# SparkFun_XBee3_Cat1_Smart_Modem_Regulate.net
KiCad netlist of a schematic drawn in EAGLE
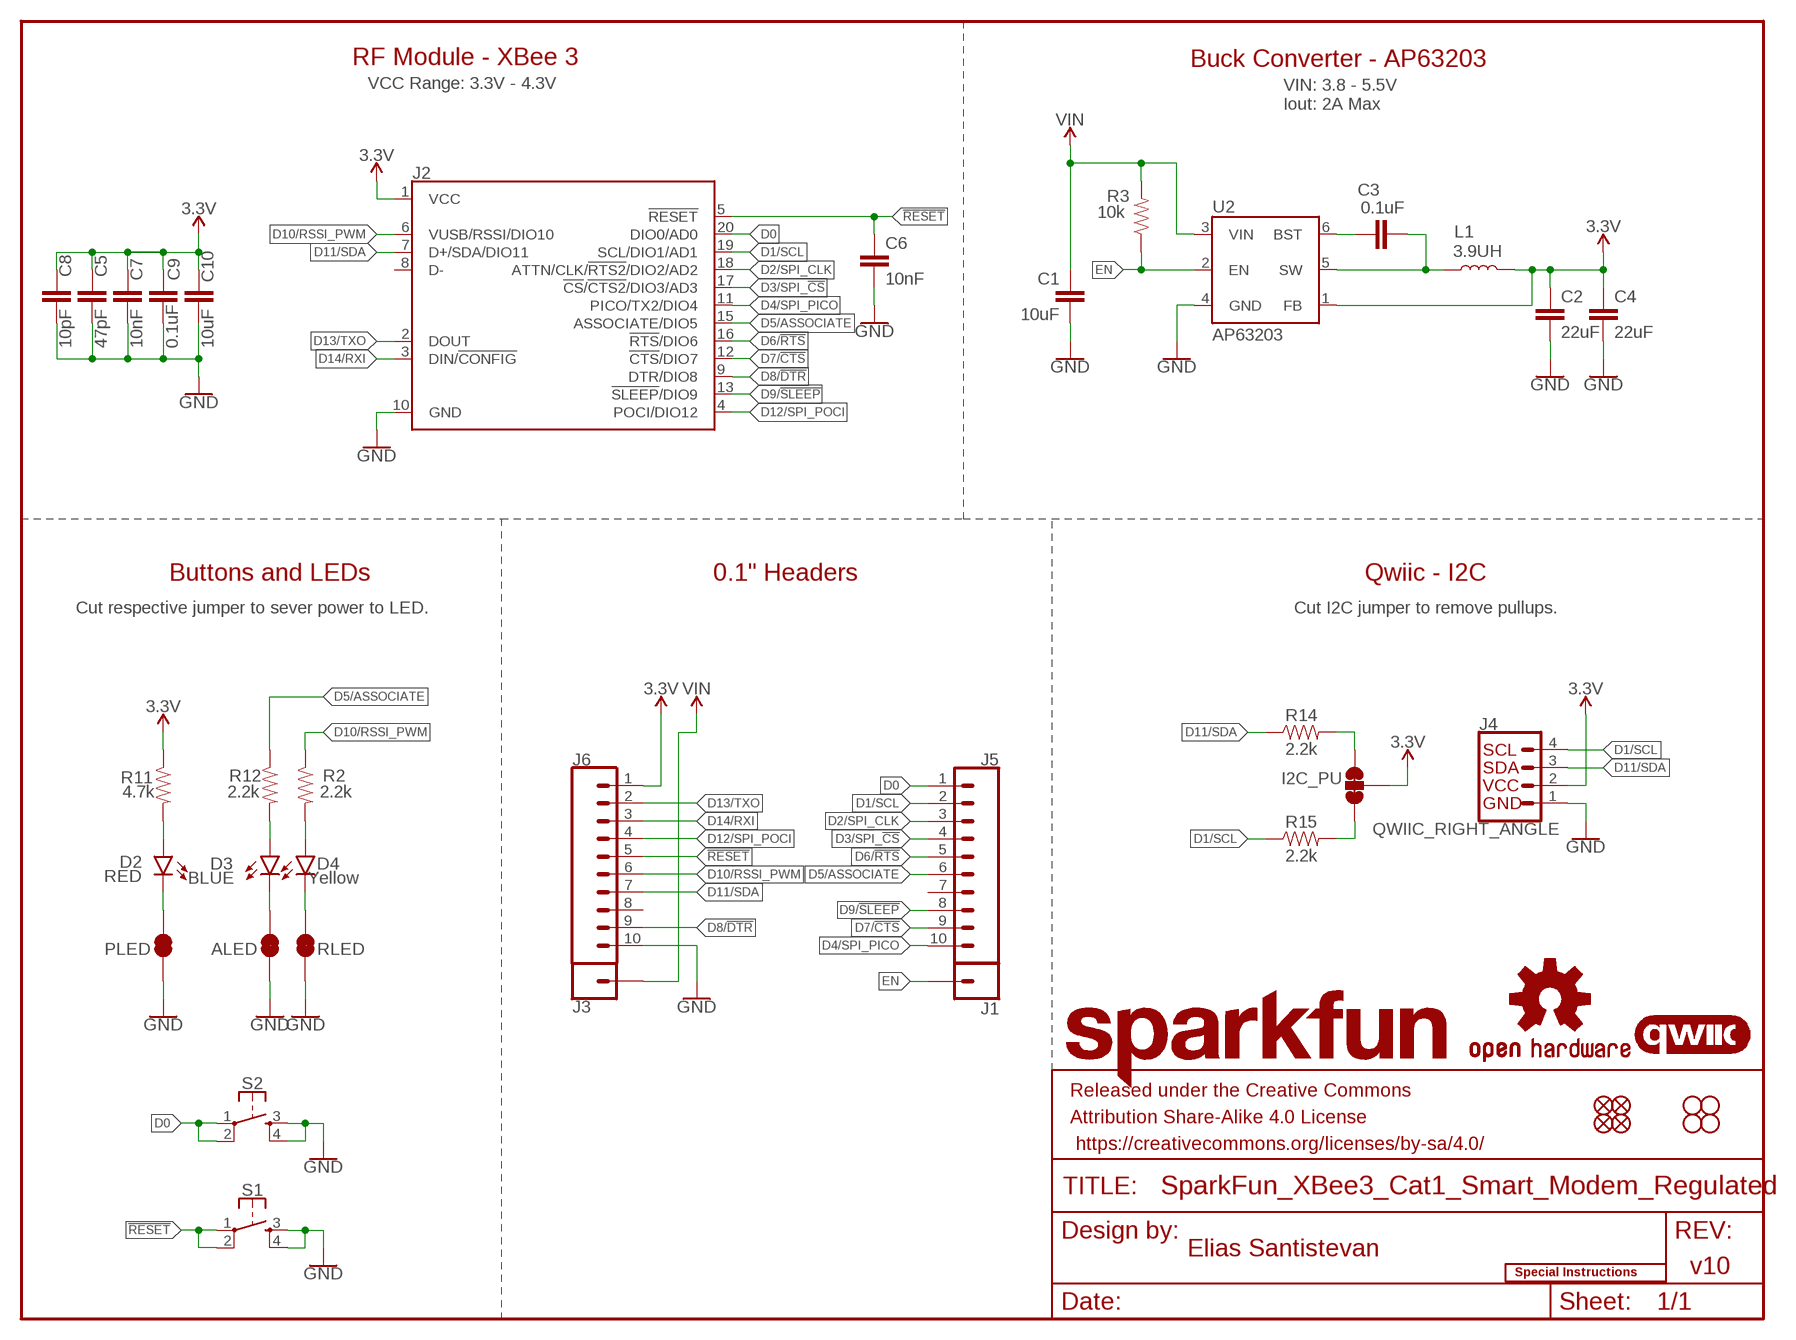
[diagram p0: schematic, sheet 1]

(export (version "E")
  (design (tool "Eeschema 10.0.6"))
  (components
    (comp (ref "ALED")
      (value "JUMPER-SMT_2_NC_TRACE_SILK")
      (footprint "eagle-import:SMT-JUMPER_2_NC_TRACE_SILK")
      (libsource (lib "eagle-import") (part "JUMPER-SMT_2_NC_TRACE_SILK"))
    )
    (comp (ref "C1")
      (value "10uF")
      (footprint "eagle-import:1210")
      (libsource (lib "eagle-import") (part "10UF-1210-50V-20%"))
    )
    (comp (ref "C2")
      (value "22uF")
      (footprint "eagle-import:0603")
      (libsource (lib "eagle-import") (part "22UF-0603-6.3V-20%"))
    )
    (comp (ref "C3")
      (value "0.1uF")
      (footprint "eagle-import:0603")
      (libsource (lib "eagle-import") (part "0.1UF-0603-25V-5%"))
    )
    (comp (ref "C4")
      (value "22uF")
      (footprint "eagle-import:0603")
      (libsource (lib "eagle-import") (part "22UF-0603-6.3V-20%"))
    )
    (comp (ref "C5")
      (value "47pF")
      (footprint "eagle-import:0603")
      (libsource (lib "eagle-import") (part "47PF-0603-50V-5%"))
    )
    (comp (ref "C6")
      (value "10nF")
      (footprint "eagle-import:0603")
      (libsource (lib "eagle-import") (part "10NF-0603-50V-10%"))
    )
    (comp (ref "C7")
      (value "10nF")
      (footprint "eagle-import:0603")
      (libsource (lib "eagle-import") (part "10NF-0603-50V-10%"))
    )
    (comp (ref "C8")
      (value "10pF")
      (footprint "eagle-import:0603")
      (libsource (lib "eagle-import") (part "10PF-0603-50V-5%"))
    )
    (comp (ref "C9")
      (value "0.1uF")
      (footprint "eagle-import:0603")
      (libsource (lib "eagle-import") (part "0.1UF-0603-25V-(+80/-20%)"))
    )
    (comp (ref "C10")
      (value "10uF")
      (footprint "eagle-import:0603")
      (libsource (lib "eagle-import") (part "10UF-0603-6.3V-20%"))
    )
    (comp (ref "D2")
      (value "RED")
      (footprint "eagle-import:LED-0603")
      (libsource (lib "eagle-import") (part "LED-RED_0603-KB"))
    )
    (comp (ref "D3")
      (value "BLUE")
      (footprint "eagle-import:LED-0603")
      (libsource (lib "eagle-import") (part "LED-BLUE0603"))
    )
    (comp (ref "D4")
      (value "Yellow")
      (footprint "eagle-import:LED-0603")
      (libsource (lib "eagle-import") (part "LED-YELLOW0603"))
    )
    (comp (ref "FD1")
      (value "FIDUCIAL1X2")
      (footprint "eagle-import:FIDUCIAL-1X2")
      (libsource (lib "eagle-import") (part "FIDUCIAL1X2"))
    )
    (comp (ref "FD2")
      (value "FIDUCIAL1X2")
      (footprint "eagle-import:FIDUCIAL-1X2")
      (libsource (lib "eagle-import") (part "FIDUCIAL1X2"))
    )
    (comp (ref "FD3")
      (value "FIDUCIAL1X2")
      (footprint "eagle-import:FIDUCIAL-1X2")
      (libsource (lib "eagle-import") (part "FIDUCIAL1X2"))
    )
    (comp (ref "FD4")
      (value "FIDUCIAL1X2")
      (footprint "eagle-import:FIDUCIAL-1X2")
      (libsource (lib "eagle-import") (part "FIDUCIAL1X2"))
    )
    (comp (ref "FRAME2")
      (value "FRAME-LETTER")
      (footprint "eagle-import:CREATIVE_COMMONS")
      (libsource (lib "eagle-import") (part "FRAME-LETTER"))
    )
    (comp (ref "H1")
      (value "STAND-OFFTIGHT")
      (footprint "eagle-import:STAND-OFF-TIGHT")
      (libsource (lib "eagle-import") (part "STAND-OFFTIGHT"))
    )
    (comp (ref "H2")
      (value "STAND-OFFTIGHT")
      (footprint "eagle-import:STAND-OFF-TIGHT")
      (libsource (lib "eagle-import") (part "STAND-OFFTIGHT"))
    )
    (comp (ref "H3")
      (value "STAND-OFFTIGHT")
      (footprint "eagle-import:STAND-OFF-TIGHT")
      (libsource (lib "eagle-import") (part "STAND-OFFTIGHT"))
    )
    (comp (ref "H4")
      (value "STAND-OFFTIGHT")
      (footprint "eagle-import:STAND-OFF-TIGHT")
      (libsource (lib "eagle-import") (part "STAND-OFFTIGHT"))
    )
    (comp (ref "I2C_PU")
      (value "JUMPER-SMT_3_2-NC_TRACE_SILK")
      (footprint "eagle-import:SMT-JUMPER_3_2-NC_TRACE_SILK")
      (libsource (lib "eagle-import") (part "JUMPER-SMT_3_2-NC_TRACE_SILK"))
    )
    (comp (ref "J1")
      (value "CONN_01PTH_NO_SILK_STAND")
      (footprint "eagle-import:1X01_NO_SILK_STAND")
      (libsource (lib "eagle-import") (part "CONN_01PTH_NO_SILK_STAND"))
    )
    (comp (ref "J2")
      (value "XBEE_UPDATEXBEE_SMD")
      (footprint "eagle-import:XBEE3-SMD")
      (libsource (lib "eagle-import") (part "XBEE_UPDATEXBEE_SMD"))
    )
    (comp (ref "J3")
      (value "CONN_01PTH_NO_SILK_STAND")
      (footprint "eagle-import:1X01_NO_SILK_STAND")
      (libsource (lib "eagle-import") (part "CONN_01PTH_NO_SILK_STAND"))
    )
    (comp (ref "J4")
      (value "QWIIC_RIGHT_ANGLE")
      (footprint "eagle-import:JST04_1MM_RA")
      (libsource (lib "eagle-import") (part "QWIIC_CONNECTORJS-1MM"))
    )
    (comp (ref "J5")
      (value "CONN_10NO_SILK_PTH_FEMALE")
      (footprint "eagle-import:1X10_NO_SILK")
      (libsource (lib "eagle-import") (part "CONN_10NO_SILK_PTH_FEMALE"))
    )
    (comp (ref "J6")
      (value "CONN_10NO_SILK_PTH_FEMALE")
      (footprint "eagle-import:1X10_NO_SILK")
      (libsource (lib "eagle-import") (part "CONN_10NO_SILK_PTH_FEMALE"))
    )
    (comp (ref "L1")
      (value "3.9UH")
      (footprint "eagle-import:INDUCTOR_3.9UH")
      (libsource (lib "eagle-import") (part "3.9UH"))
    )
    (comp (ref "LOGO1")
      (value "SPECIAL_INSTRUCTIONS-ORDERING")
      (footprint "eagle-import:ORDERING_INSTRUCTIONS")
      (libsource (lib "eagle-import") (part "SPECIAL_INSTRUCTIONS-ORDERING"))
    )
    (comp (ref "LOGO2")
      (value "OSHW-LOGOS")
      (footprint "eagle-import:OSHW-LOGO-S")
      (libsource (lib "eagle-import") (part "OSHW-LOGOS"))
    )
    (comp (ref "LOGO3")
      (value "QWIIC_LOGO_4MM")
      (footprint "eagle-import:QWIIC_4MM")
      (libsource (lib "eagle-import") (part "QWIIC_LOGO_4MM"))
    )
    (comp (ref "LOGO4")
      (value "SFE_LOGO_NAMEBLANK")
      (footprint "eagle-import:BLANK")
      (libsource (lib "eagle-import") (part "SFE_LOGO_NAMEBLANK"))
    )
    (comp (ref "PLED")
      (value "JUMPER-SMT_2_NC_TRACE_SILK")
      (footprint "eagle-import:SMT-JUMPER_2_NC_TRACE_SILK")
      (libsource (lib "eagle-import") (part "JUMPER-SMT_2_NC_TRACE_SILK"))
    )
    (comp (ref "R2")
      (value "2.2k")
      (footprint "eagle-import:0603")
      (libsource (lib "eagle-import") (part "2.2KOHM-0603-1/10W-1%"))
    )
    (comp (ref "R3")
      (value "10k")
      (footprint "eagle-import:0603")
      (libsource (lib "eagle-import") (part "10KOHM-0603-1/10W-1%"))
    )
    (comp (ref "R11")
      (value "4.7k")
      (footprint "eagle-import:0603")
      (libsource (lib "eagle-import") (part "4.7KOHM-0603-1/10W-1%"))
    )
    (comp (ref "R12")
      (value "2.2k")
      (footprint "eagle-import:0603")
      (libsource (lib "eagle-import") (part "2.2KOHM-0603-1/10W-1%"))
    )
    (comp (ref "R14")
      (value "2.2k")
      (footprint "eagle-import:0603")
      (libsource (lib "eagle-import") (part "2.2KOHM-0603-1/10W-1%"))
    )
    (comp (ref "R15")
      (value "2.2k")
      (footprint "eagle-import:0603")
      (libsource (lib "eagle-import") (part "2.2KOHM-0603-1/10W-1%"))
    )
    (comp (ref "RLED")
      (value "JUMPER-SMT_2_NC_TRACE_SILK")
      (footprint "eagle-import:SMT-JUMPER_2_NC_TRACE_SILK")
      (libsource (lib "eagle-import") (part "JUMPER-SMT_2_NC_TRACE_SILK"))
    )
    (comp (ref "S1")
      (value "MOMENTARY-SWITCH-SPST-2-SMD-5.2MM-TALL")
      (footprint "eagle-import:TACTILE_SWITCH_SMD_5.2MM")
      (libsource (lib "eagle-import") (part "MOMENTARY-SWITCH-SPST-2-SMD-5.2MM-TALL"))
    )
    (comp (ref "S2")
      (value "MOMENTARY-SWITCH-SPST-2-SMD-5.2MM-TALL")
      (footprint "eagle-import:TACTILE_SWITCH_SMD_5.2MM")
      (libsource (lib "eagle-import") (part "MOMENTARY-SWITCH-SPST-2-SMD-5.2MM-TALL"))
    )
    (comp (ref "U2")
      (value "AP63203")
      (footprint "eagle-import:SOT23-6")
      (libsource (lib "eagle-import") (part "AP63203"))
    )
  )
  (nets
    (net (code "1") (name "/D3{slash}SPI_~{CS}") (class "Default")
      (node (ref "J2") (pin "17") (pinfunction "~{CS}/~{CTS2}/DIO3/AD3_17") (pintype "bidirectional"))
      (node (ref "J5") (pin "4") (pinfunction "4_4") (pintype "passive"))
    )
    (net (code "2") (name "/D6{slash}~{RTS}") (class "Default")
      (node (ref "J2") (pin "16") (pinfunction "~{RTS}/DIO6_16") (pintype "input"))
      (node (ref "J5") (pin "5") (pinfunction "5_5") (pintype "passive"))
    )
    (net (code "3") (name "/D7{slash}~{CTS}") (class "Default")
      (node (ref "J2") (pin "12") (pinfunction "~{CTS}/DIO7_12") (pintype "output"))
      (node (ref "J5") (pin "9") (pinfunction "9_9") (pintype "passive"))
    )
    (net (code "4") (name "/D8{slash}~{DTR}") (class "Default")
      (node (ref "J2") (pin "9") (pinfunction "DTR/DIO8_9") (pintype "bidirectional"))
      (node (ref "J6") (pin "9") (pinfunction "9_9") (pintype "passive"))
    )
    (net (code "5") (name "/D9{slash}~{SLEEP}") (class "Default")
      (node (ref "J2") (pin "13") (pinfunction "~{SLEEP}/DIO9_13") (pintype "bidirectional"))
      (node (ref "J5") (pin "8") (pinfunction "8_8") (pintype "passive"))
    )
    (net (code "6") (name "/~{RESET}") (class "Default")
      (node (ref "C6") (pin "1") (pinfunction "1_1") (pintype "passive"))
      (node (ref "J2") (pin "5") (pinfunction "~{RESET}_5") (pintype "input"))
      (node (ref "J6") (pin "5") (pinfunction "5_5") (pintype "passive"))
      (node (ref "S1") (pin "1") (pinfunction "1_1") (pintype "passive"))
      (node (ref "S1") (pin "2") (pinfunction "2_2") (pintype "passive"))
    )
    (net (code "7") (name "3.3V") (class "Default")
      (node (ref "C10") (pin "1") (pinfunction "1_1") (pintype "passive"))
      (node (ref "C2") (pin "1") (pinfunction "1_1") (pintype "passive"))
      (node (ref "C4") (pin "1") (pinfunction "1_1") (pintype "passive"))
      (node (ref "C5") (pin "1") (pinfunction "1_1") (pintype "passive"))
      (node (ref "C7") (pin "1") (pinfunction "1_1") (pintype "passive"))
      (node (ref "C8") (pin "1") (pinfunction "1_1") (pintype "passive"))
      (node (ref "C9") (pin "1") (pinfunction "1_1") (pintype "passive"))
      (node (ref "I2C_PU") (pin "2") (pinfunction "2_2") (pintype "passive"))
      (node (ref "J2") (pin "1") (pinfunction "VCC_1") (pintype "power_in"))
      (node (ref "J4") (pin "2") (pinfunction "2_2") (pintype "power_in"))
      (node (ref "J6") (pin "1") (pinfunction "1_1") (pintype "passive"))
      (node (ref "L1") (pin "P$2") (pinfunction "2_P$2") (pintype "passive"))
      (node (ref "R11") (pin "1") (pinfunction "1_1") (pintype "passive"))
      (node (ref "U2") (pin "1") (pinfunction "FB_1") (pintype "bidirectional"))
    )
    (net (code "8") (name "D0") (class "Default")
      (node (ref "J2") (pin "20") (pinfunction "DIO0/AD0_20") (pintype "bidirectional"))
      (node (ref "J5") (pin "1") (pinfunction "1_1") (pintype "passive"))
      (node (ref "S2") (pin "1") (pinfunction "1_1") (pintype "passive"))
      (node (ref "S2") (pin "2") (pinfunction "2_2") (pintype "passive"))
    )
    (net (code "9") (name "D1{slash}SCL") (class "Default")
      (node (ref "J2") (pin "19") (pinfunction "SCL/DIO1/AD1_19") (pintype "bidirectional"))
      (node (ref "J4") (pin "4") (pinfunction "4_4") (pintype "passive"))
      (node (ref "J5") (pin "2") (pinfunction "2_2") (pintype "passive"))
      (node (ref "R15") (pin "1") (pinfunction "1_1") (pintype "passive"))
    )
    (net (code "10") (name "D2{slash}SPI_CLK") (class "Default")
      (node (ref "J2") (pin "18") (pinfunction "ATTN/CLK/~{RTS2}/DIO2/AD2_18") (pintype "bidirectional"))
      (node (ref "J5") (pin "3") (pinfunction "3_3") (pintype "passive"))
    )
    (net (code "11") (name "D4{slash}SPI_PICO") (class "Default")
      (node (ref "J2") (pin "11") (pinfunction "PICO/TX2/DIO4_11") (pintype "bidirectional"))
      (node (ref "J5") (pin "10") (pinfunction "10_10") (pintype "passive"))
    )
    (net (code "12") (name "D5{slash}ASSOCIATE") (class "Default")
      (node (ref "J2") (pin "15") (pinfunction "ASSOCIATE/DIO5_15") (pintype "bidirectional"))
      (node (ref "J5") (pin "6") (pinfunction "6_6") (pintype "passive"))
      (node (ref "R12") (pin "1") (pinfunction "1_1") (pintype "passive"))
    )
    (net (code "13") (name "D10{slash}RSSI_PWM") (class "Default")
      (node (ref "J2") (pin "6") (pinfunction "VUSB/RSSI/DIO10_6") (pintype "bidirectional"))
      (node (ref "J6") (pin "6") (pinfunction "6_6") (pintype "passive"))
      (node (ref "R2") (pin "1") (pinfunction "1_1") (pintype "passive"))
    )
    (net (code "14") (name "D11{slash}SDA") (class "Default")
      (node (ref "J2") (pin "7") (pinfunction "D+/SDA/DIO11_7") (pintype "bidirectional"))
      (node (ref "J4") (pin "3") (pinfunction "3_3") (pintype "passive"))
      (node (ref "J6") (pin "7") (pinfunction "7_7") (pintype "passive"))
      (node (ref "R14") (pin "1") (pinfunction "1_1") (pintype "passive"))
    )
    (net (code "15") (name "D12{slash}SPI_POCI") (class "Default")
      (node (ref "J2") (pin "4") (pinfunction "POCI/DIO12_4") (pintype "bidirectional"))
      (node (ref "J6") (pin "4") (pinfunction "4_4") (pintype "passive"))
    )
    (net (code "16") (name "D13{slash}TXO") (class "Default")
      (node (ref "J2") (pin "2") (pinfunction "DOUT_2") (pintype "output"))
      (node (ref "J6") (pin "2") (pinfunction "2_2") (pintype "passive"))
    )
    (net (code "17") (name "D14{slash}RXI") (class "Default")
      (node (ref "J2") (pin "3") (pinfunction "DIN/~{CONFIG}_3") (pintype "input"))
      (node (ref "J6") (pin "3") (pinfunction "3_3") (pintype "passive"))
    )
    (net (code "18") (name "EN") (class "Default")
      (node (ref "J1") (pin "1") (pinfunction "1_1") (pintype "passive"))
      (node (ref "R3") (pin "1") (pinfunction "1_1") (pintype "passive"))
      (node (ref "U2") (pin "2") (pinfunction "EN_2") (pintype "bidirectional"))
    )
    (net (code "19") (name "GND") (class "Default")
      (node (ref "ALED") (pin "1") (pinfunction "1_1") (pintype "passive"))
      (node (ref "C1") (pin "2") (pinfunction "2_2") (pintype "passive"))
      (node (ref "C10") (pin "2") (pinfunction "2_2") (pintype "passive"))
      (node (ref "C2") (pin "2") (pinfunction "2_2") (pintype "passive"))
      (node (ref "C4") (pin "2") (pinfunction "2_2") (pintype "passive"))
      (node (ref "C5") (pin "2") (pinfunction "2_2") (pintype "passive"))
      (node (ref "C6") (pin "2") (pinfunction "2_2") (pintype "passive"))
      (node (ref "C7") (pin "2") (pinfunction "2_2") (pintype "passive"))
      (node (ref "C8") (pin "2") (pinfunction "2_2") (pintype "passive"))
      (node (ref "C9") (pin "2") (pinfunction "2_2") (pintype "passive"))
      (node (ref "J2") (pin "10") (pinfunction "GND_10") (pintype "power_in"))
      (node (ref "J4") (pin "1") (pinfunction "1_1") (pintype "power_in"))
      (node (ref "J6") (pin "10") (pinfunction "10_10") (pintype "passive"))
      (node (ref "PLED") (pin "1") (pinfunction "1_1") (pintype "passive"))
      (node (ref "RLED") (pin "1") (pinfunction "1_1") (pintype "passive"))
      (node (ref "S1") (pin "3") (pinfunction "3_3") (pintype "passive"))
      (node (ref "S1") (pin "4") (pinfunction "4_4") (pintype "passive"))
      (node (ref "S2") (pin "3") (pinfunction "3_3") (pintype "passive"))
      (node (ref "S2") (pin "4") (pinfunction "4_4") (pintype "passive"))
      (node (ref "U2") (pin "4") (pinfunction "GND_4") (pintype "bidirectional"))
    )
    (net (code "20") (name "Net-(ALED-Pad2)") (class "Default")
      (node (ref "ALED") (pin "2") (pinfunction "2_2") (pintype "passive"))
      (node (ref "D3") (pin "C") (pinfunction "C_C") (pintype "passive"))
    )
    (net (code "21") (name "Net-(D2-PadA)") (class "Default")
      (node (ref "D2") (pin "A") (pinfunction "A_A") (pintype "passive"))
      (node (ref "R11") (pin "2") (pinfunction "2_2") (pintype "passive"))
    )
    (net (code "22") (name "Net-(D2-PadC)") (class "Default")
      (node (ref "D2") (pin "C") (pinfunction "C_C") (pintype "passive"))
      (node (ref "PLED") (pin "2") (pinfunction "2_2") (pintype "passive"))
    )
    (net (code "23") (name "Net-(D3-PadA)") (class "Default")
      (node (ref "D3") (pin "A") (pinfunction "A_A") (pintype "passive"))
      (node (ref "R12") (pin "2") (pinfunction "2_2") (pintype "passive"))
    )
    (net (code "24") (name "Net-(D4-PadA)") (class "Default")
      (node (ref "D4") (pin "A") (pinfunction "A_A") (pintype "passive"))
      (node (ref "R2") (pin "2") (pinfunction "2_2") (pintype "passive"))
    )
    (net (code "25") (name "Net-(D4-PadC)") (class "Default")
      (node (ref "D4") (pin "C") (pinfunction "C_C") (pintype "passive"))
      (node (ref "RLED") (pin "2") (pinfunction "2_2") (pintype "passive"))
    )
    (net (code "26") (name "Net-(I2C_PU-Pad1)") (class "Default")
      (node (ref "I2C_PU") (pin "1") (pinfunction "1_1") (pintype "passive"))
      (node (ref "R15") (pin "2") (pinfunction "2_2") (pintype "passive"))
    )
    (net (code "27") (name "Net-(I2C_PU-Pad3)") (class "Default")
      (node (ref "I2C_PU") (pin "3") (pinfunction "3_3") (pintype "passive"))
      (node (ref "R14") (pin "2") (pinfunction "2_2") (pintype "passive"))
    )
    (net (code "28") (name "Net-(L1-1)") (class "Default")
      (node (ref "C3") (pin "2") (pinfunction "2_2") (pintype "passive"))
      (node (ref "L1") (pin "P$1") (pinfunction "1_P$1") (pintype "passive"))
      (node (ref "U2") (pin "5") (pinfunction "SW_5") (pintype "bidirectional"))
    )
    (net (code "29") (name "Net-(U2-BST)") (class "Default")
      (node (ref "C3") (pin "1") (pinfunction "1_1") (pintype "passive"))
      (node (ref "U2") (pin "6") (pinfunction "BST_6") (pintype "bidirectional"))
    )
    (net (code "30") (name "VIN") (class "Default")
      (node (ref "C1") (pin "1") (pinfunction "1_1") (pintype "passive"))
      (node (ref "J3") (pin "1") (pinfunction "1_1") (pintype "passive"))
      (node (ref "R3") (pin "2") (pinfunction "2_2") (pintype "passive"))
      (node (ref "U2") (pin "3") (pinfunction "VIN_3") (pintype "bidirectional"))
    )
    (net (code "31") (name "unconnected-(J2-D--Pad8)") (class "Default")
      (node (ref "J2") (pin "8") (pinfunction "D-_8") (pintype "bidirectional"))
    )
    (net (code "32") (name "unconnected-(J5-Pad7)") (class "Default")
      (node (ref "J5") (pin "7") (pinfunction "7_7") (pintype "passive"))
    )
    (net (code "33") (name "unconnected-(J6-Pad8)") (class "Default")
      (node (ref "J6") (pin "8") (pinfunction "8_8") (pintype "passive"))
    )
  )
)
